# 16n-midijack.net
KiCad netlist of a schematic drawn in EAGLE
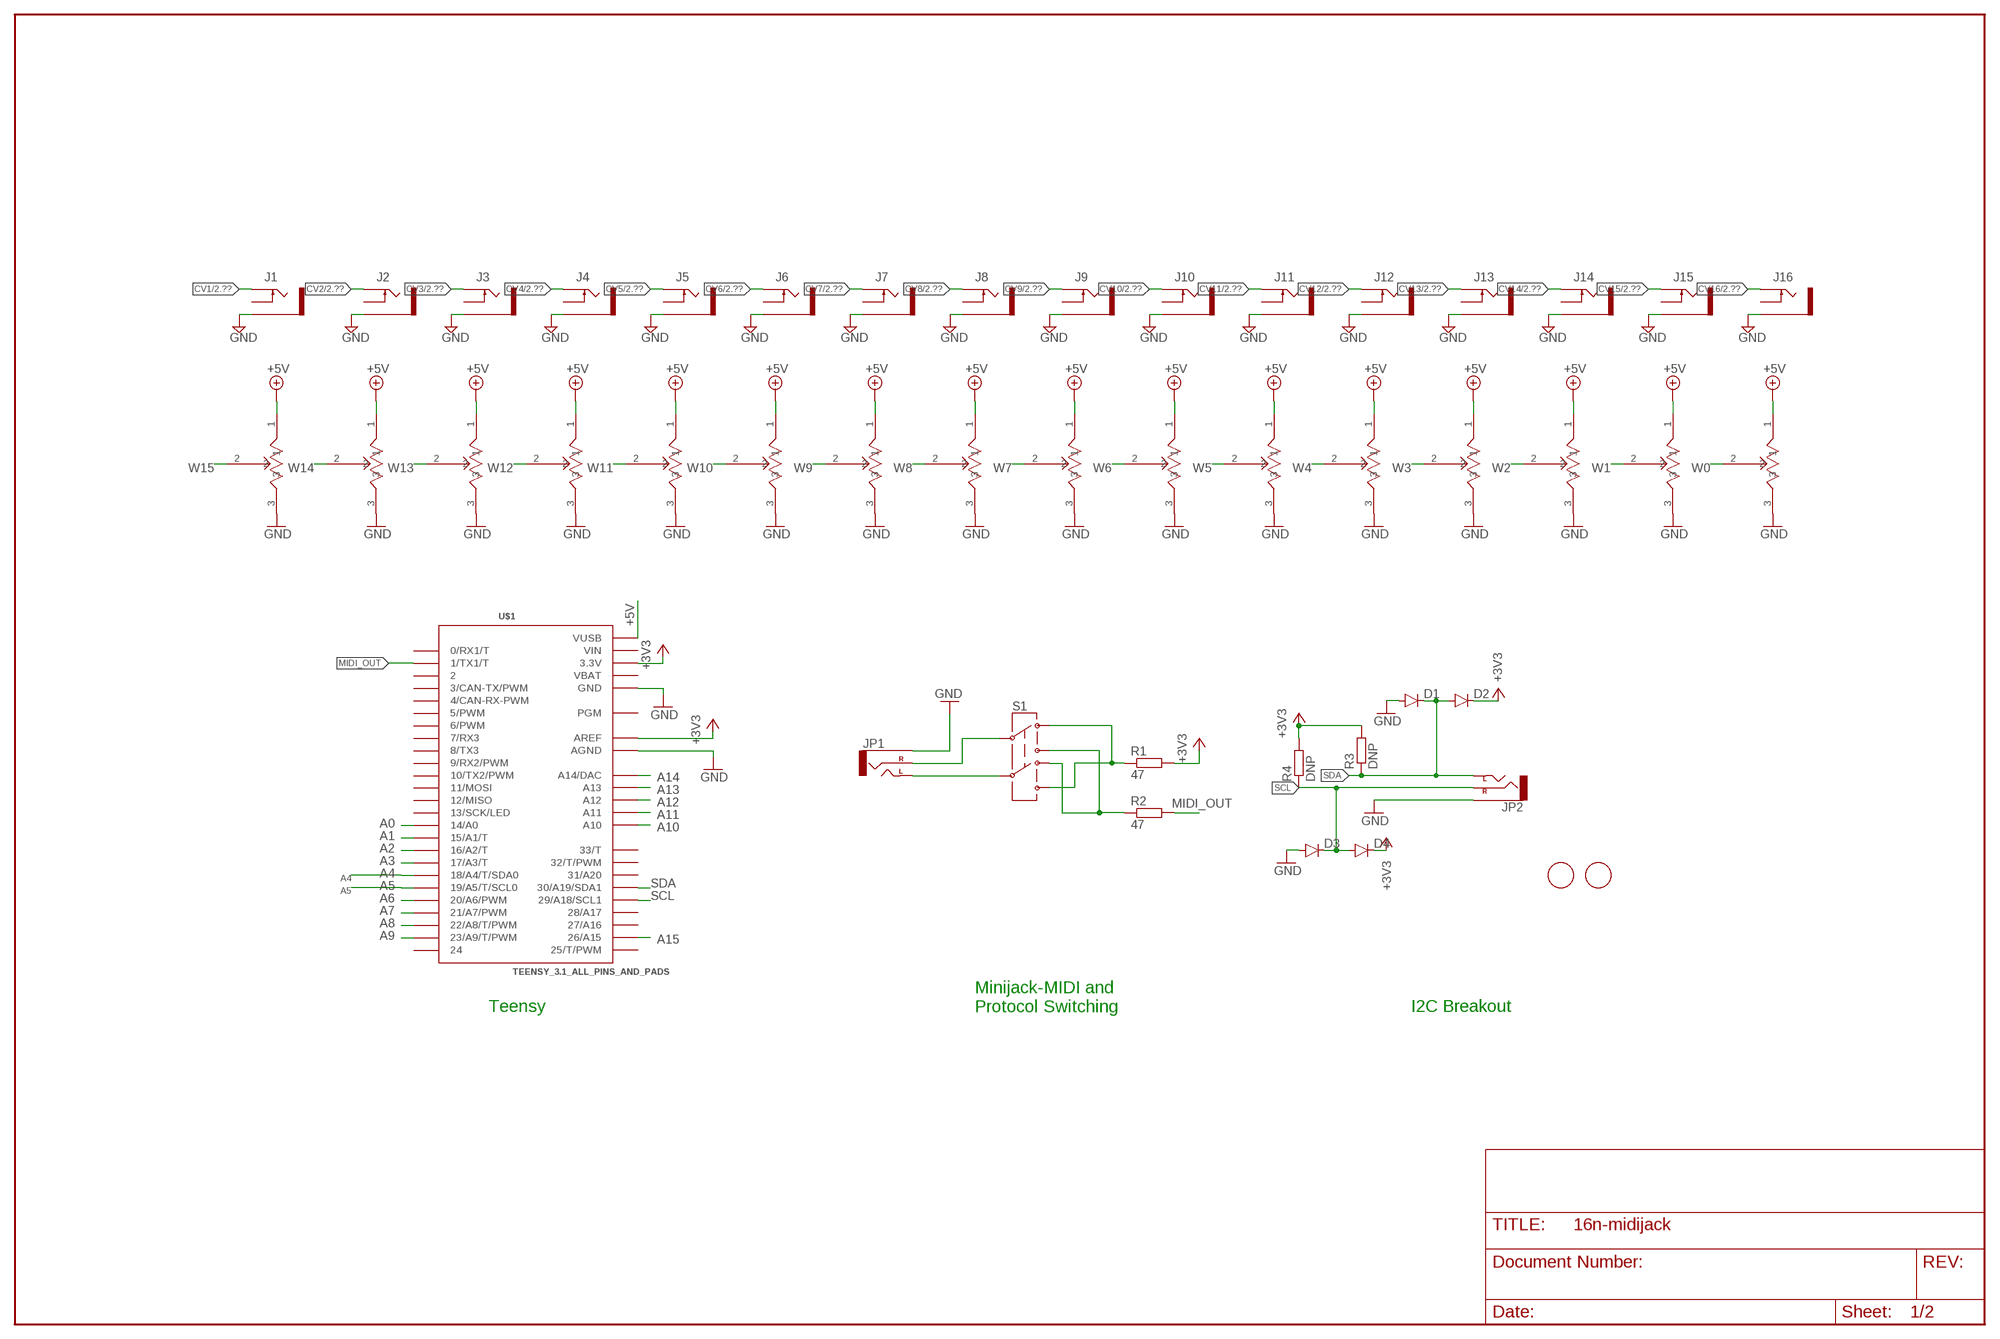
[diagram p0: schematic, sheet 1]
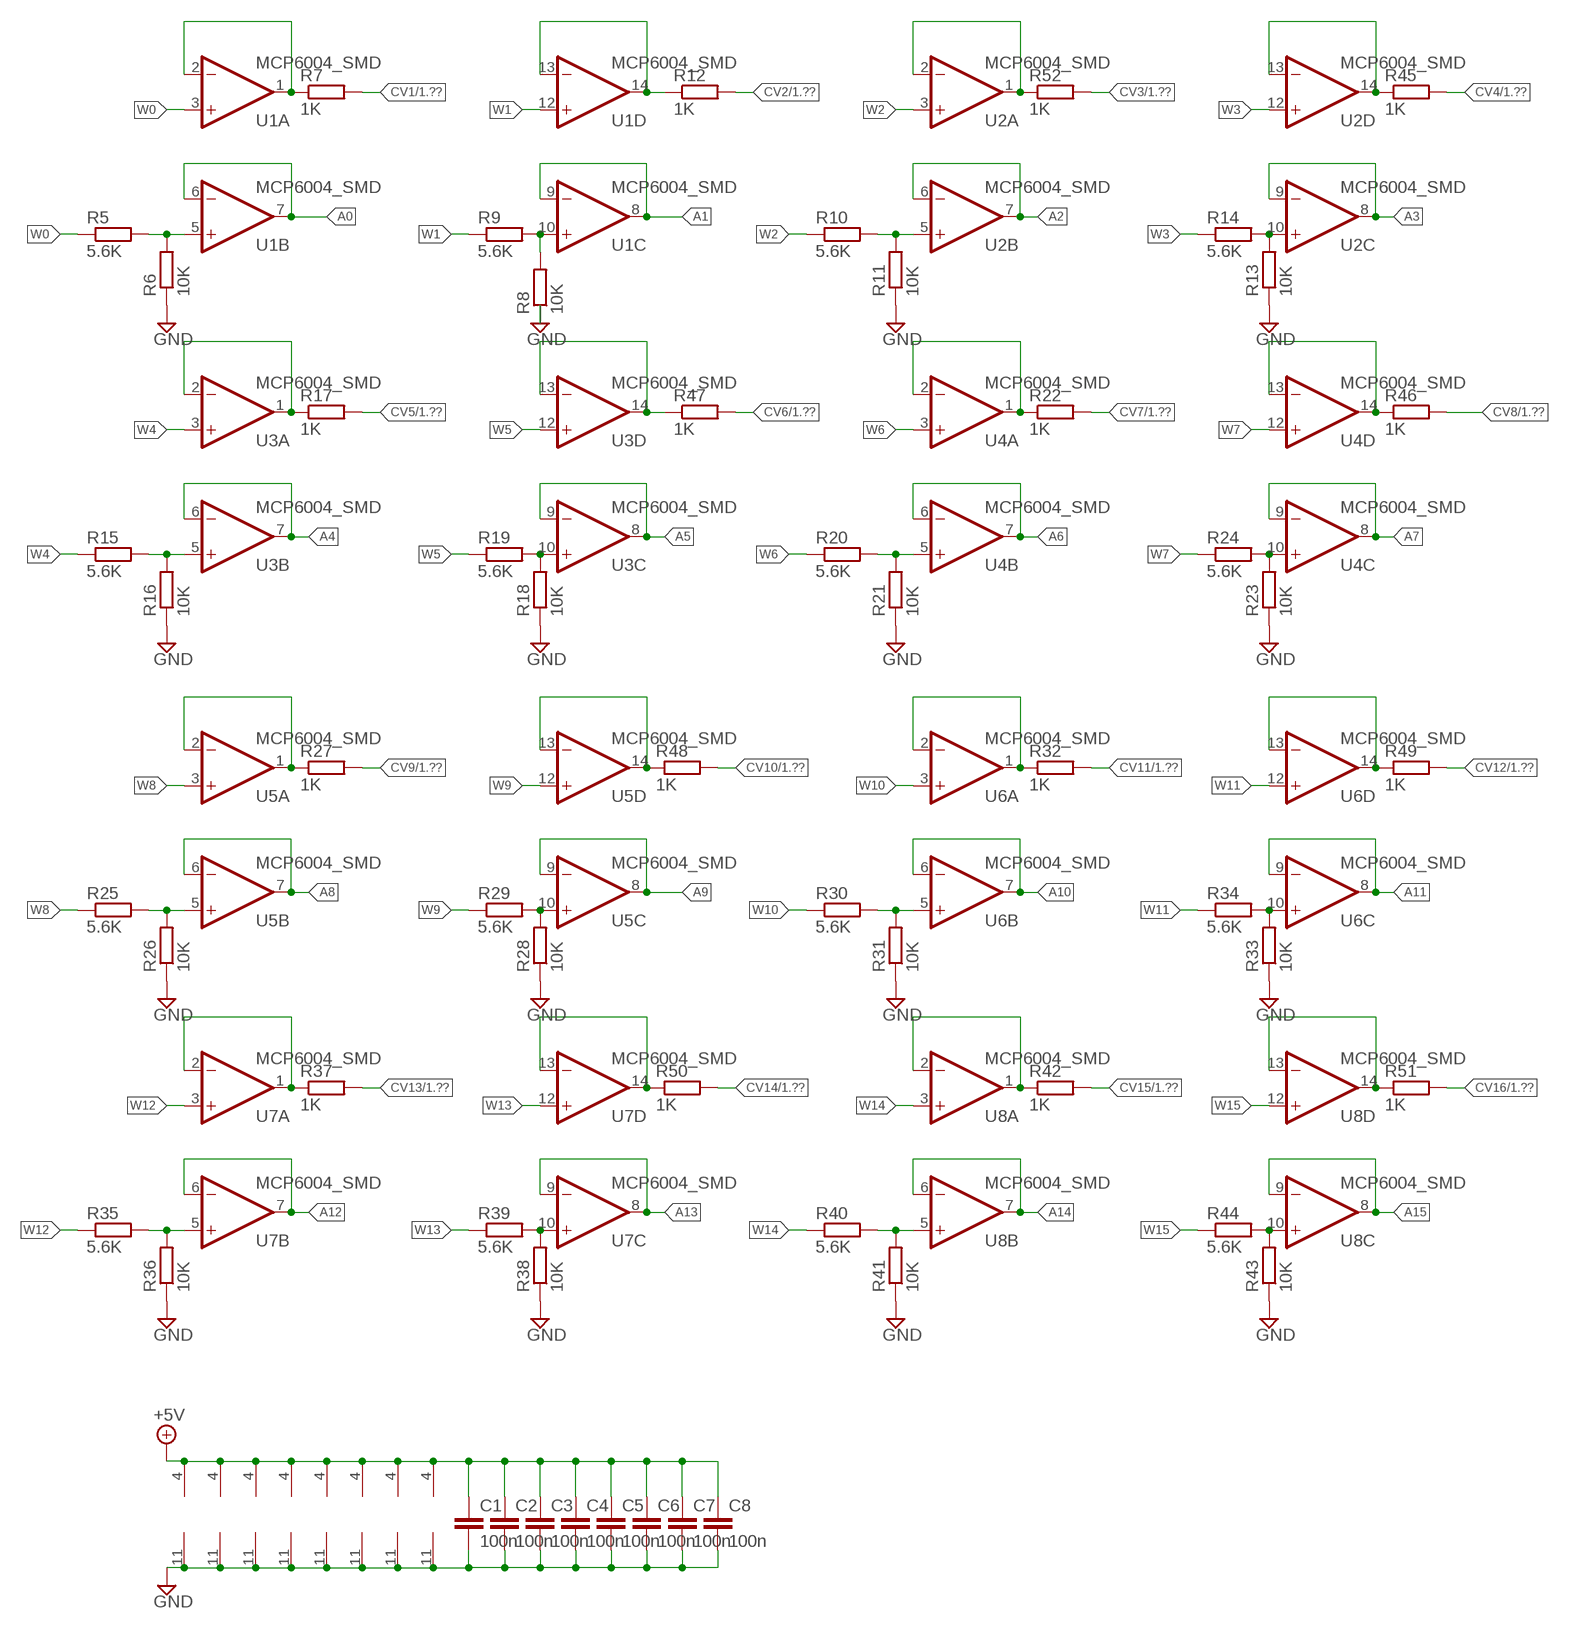
[diagram p1: schematic, sheet 2]

(export (version "E")
  (design (tool "Eeschema 10.0.6"))
  (components
    (comp (ref "C1")
      (value "100n")
      (footprint "eagle-import:C0805")
      (libsource (lib "eagle-import") (part "C-EUC0805"))
    )
    (comp (ref "C2")
      (value "100n")
      (footprint "eagle-import:C0805")
      (libsource (lib "eagle-import") (part "C-EUC0805"))
    )
    (comp (ref "C3")
      (value "100n")
      (footprint "eagle-import:C0805")
      (libsource (lib "eagle-import") (part "C-EUC0805"))
    )
    (comp (ref "C4")
      (value "100n")
      (footprint "eagle-import:C0805")
      (libsource (lib "eagle-import") (part "C-EUC0805"))
    )
    (comp (ref "C5")
      (value "100n")
      (footprint "eagle-import:C0805")
      (libsource (lib "eagle-import") (part "C-EUC0805"))
    )
    (comp (ref "C6")
      (value "100n")
      (footprint "eagle-import:C0805")
      (libsource (lib "eagle-import") (part "C-EUC0805"))
    )
    (comp (ref "C7")
      (value "100n")
      (footprint "eagle-import:C0805")
      (libsource (lib "eagle-import") (part "C-EUC0805"))
    )
    (comp (ref "C8")
      (value "100n")
      (footprint "eagle-import:C0805")
      (libsource (lib "eagle-import") (part "C-EUC0805"))
    )
    (comp (ref "R5")
      (value "5.6K")
      (footprint "eagle-import:R0805")
      (libsource (lib "eagle-import") (part "R-EU_R0805"))
    )
    (comp (ref "R6")
      (value "10K")
      (footprint "eagle-import:R0805")
      (libsource (lib "eagle-import") (part "R-EU_R0805"))
    )
    (comp (ref "R7")
      (value "1K")
      (footprint "eagle-import:R0805")
      (libsource (lib "eagle-import") (part "R-EU_R0805"))
    )
    (comp (ref "R8")
      (value "10K")
      (footprint "eagle-import:R0805")
      (libsource (lib "eagle-import") (part "R-EU_R0805"))
    )
    (comp (ref "R9")
      (value "5.6K")
      (footprint "eagle-import:R0805")
      (libsource (lib "eagle-import") (part "R-EU_R0805"))
    )
    (comp (ref "R10")
      (value "5.6K")
      (footprint "eagle-import:R0805")
      (libsource (lib "eagle-import") (part "R-EU_R0805"))
    )
    (comp (ref "R11")
      (value "10K")
      (footprint "eagle-import:R0805")
      (libsource (lib "eagle-import") (part "R-EU_R0805"))
    )
    (comp (ref "R12")
      (value "1K")
      (footprint "eagle-import:R0805")
      (libsource (lib "eagle-import") (part "R-EU_R0805"))
    )
    (comp (ref "R13")
      (value "10K")
      (footprint "eagle-import:R0805")
      (libsource (lib "eagle-import") (part "R-EU_R0805"))
    )
    (comp (ref "R14")
      (value "5.6K")
      (footprint "eagle-import:R0805")
      (libsource (lib "eagle-import") (part "R-EU_R0805"))
    )
    (comp (ref "R15")
      (value "5.6K")
      (footprint "eagle-import:R0805")
      (libsource (lib "eagle-import") (part "R-EU_R0805"))
    )
    (comp (ref "R16")
      (value "10K")
      (footprint "eagle-import:R0805")
      (libsource (lib "eagle-import") (part "R-EU_R0805"))
    )
    (comp (ref "R17")
      (value "1K")
      (footprint "eagle-import:R0805")
      (libsource (lib "eagle-import") (part "R-EU_R0805"))
    )
    (comp (ref "R18")
      (value "10K")
      (footprint "eagle-import:R0805")
      (libsource (lib "eagle-import") (part "R-EU_R0805"))
    )
    (comp (ref "R19")
      (value "5.6K")
      (footprint "eagle-import:R0805")
      (libsource (lib "eagle-import") (part "R-EU_R0805"))
    )
    (comp (ref "R20")
      (value "5.6K")
      (footprint "eagle-import:R0805")
      (libsource (lib "eagle-import") (part "R-EU_R0805"))
    )
    (comp (ref "R21")
      (value "10K")
      (footprint "eagle-import:R0805")
      (libsource (lib "eagle-import") (part "R-EU_R0805"))
    )
    (comp (ref "R22")
      (value "1K")
      (footprint "eagle-import:R0805")
      (libsource (lib "eagle-import") (part "R-EU_R0805"))
    )
    (comp (ref "R23")
      (value "10K")
      (footprint "eagle-import:R0805")
      (libsource (lib "eagle-import") (part "R-EU_R0805"))
    )
    (comp (ref "R24")
      (value "5.6K")
      (footprint "eagle-import:R0805")
      (libsource (lib "eagle-import") (part "R-EU_R0805"))
    )
    (comp (ref "R25")
      (value "5.6K")
      (footprint "eagle-import:R0805")
      (libsource (lib "eagle-import") (part "R-EU_R0805"))
    )
    (comp (ref "R26")
      (value "10K")
      (footprint "eagle-import:R0805")
      (libsource (lib "eagle-import") (part "R-EU_R0805"))
    )
    (comp (ref "R27")
      (value "1K")
      (footprint "eagle-import:R0805")
      (libsource (lib "eagle-import") (part "R-EU_R0805"))
    )
    (comp (ref "R28")
      (value "10K")
      (footprint "eagle-import:R0805")
      (libsource (lib "eagle-import") (part "R-EU_R0805"))
    )
    (comp (ref "R29")
      (value "5.6K")
      (footprint "eagle-import:R0805")
      (libsource (lib "eagle-import") (part "R-EU_R0805"))
    )
    (comp (ref "R30")
      (value "5.6K")
      (footprint "eagle-import:R0805")
      (libsource (lib "eagle-import") (part "R-EU_R0805"))
    )
    (comp (ref "R31")
      (value "10K")
      (footprint "eagle-import:R0805")
      (libsource (lib "eagle-import") (part "R-EU_R0805"))
    )
    (comp (ref "R32")
      (value "1K")
      (footprint "eagle-import:R0805")
      (libsource (lib "eagle-import") (part "R-EU_R0805"))
    )
    (comp (ref "R33")
      (value "10K")
      (footprint "eagle-import:R0805")
      (libsource (lib "eagle-import") (part "R-EU_R0805"))
    )
    (comp (ref "R34")
      (value "5.6K")
      (footprint "eagle-import:R0805")
      (libsource (lib "eagle-import") (part "R-EU_R0805"))
    )
    (comp (ref "R35")
      (value "5.6K")
      (footprint "eagle-import:R0805")
      (libsource (lib "eagle-import") (part "R-EU_R0805"))
    )
    (comp (ref "R36")
      (value "10K")
      (footprint "eagle-import:R0805")
      (libsource (lib "eagle-import") (part "R-EU_R0805"))
    )
    (comp (ref "R37")
      (value "1K")
      (footprint "eagle-import:R0805")
      (libsource (lib "eagle-import") (part "R-EU_R0805"))
    )
    (comp (ref "R38")
      (value "10K")
      (footprint "eagle-import:R0805")
      (libsource (lib "eagle-import") (part "R-EU_R0805"))
    )
    (comp (ref "R39")
      (value "5.6K")
      (footprint "eagle-import:R0805")
      (libsource (lib "eagle-import") (part "R-EU_R0805"))
    )
    (comp (ref "R40")
      (value "5.6K")
      (footprint "eagle-import:R0805")
      (libsource (lib "eagle-import") (part "R-EU_R0805"))
    )
    (comp (ref "R41")
      (value "10K")
      (footprint "eagle-import:R0805")
      (libsource (lib "eagle-import") (part "R-EU_R0805"))
    )
    (comp (ref "R42")
      (value "1K")
      (footprint "eagle-import:R0805")
      (libsource (lib "eagle-import") (part "R-EU_R0805"))
    )
    (comp (ref "R43")
      (value "10K")
      (footprint "eagle-import:R0805")
      (libsource (lib "eagle-import") (part "R-EU_R0805"))
    )
    (comp (ref "R44")
      (value "5.6K")
      (footprint "eagle-import:R0805")
      (libsource (lib "eagle-import") (part "R-EU_R0805"))
    )
    (comp (ref "R45")
      (value "1K")
      (footprint "eagle-import:R0805")
      (libsource (lib "eagle-import") (part "R-EU_R0805"))
    )
    (comp (ref "R46")
      (value "1K")
      (footprint "eagle-import:R0805")
      (libsource (lib "eagle-import") (part "R-EU_R0805"))
    )
    (comp (ref "R47")
      (value "1K")
      (footprint "eagle-import:R0805")
      (libsource (lib "eagle-import") (part "R-EU_R0805"))
    )
    (comp (ref "R48")
      (value "1K")
      (footprint "eagle-import:R0805")
      (libsource (lib "eagle-import") (part "R-EU_R0805"))
    )
    (comp (ref "R49")
      (value "1K")
      (footprint "eagle-import:R0805")
      (libsource (lib "eagle-import") (part "R-EU_R0805"))
    )
    (comp (ref "R50")
      (value "1K")
      (footprint "eagle-import:R0805")
      (libsource (lib "eagle-import") (part "R-EU_R0805"))
    )
    (comp (ref "R51")
      (value "1K")
      (footprint "eagle-import:R0805")
      (libsource (lib "eagle-import") (part "R-EU_R0805"))
    )
    (comp (ref "R52")
      (value "1K")
      (footprint "eagle-import:R0805")
      (libsource (lib "eagle-import") (part "R-EU_R0805"))
    )
    (comp (ref "U1")
      (value "MCP6004_SMD")
      (footprint "eagle-import:SO14")
      (libsource (lib "eagle-import") (part "MCP6004_SMD"))
    )
    (comp (ref "U2")
      (value "MCP6004_SMD")
      (footprint "eagle-import:SO14")
      (libsource (lib "eagle-import") (part "MCP6004_SMD"))
    )
    (comp (ref "U3")
      (value "MCP6004_SMD")
      (footprint "eagle-import:SO14")
      (libsource (lib "eagle-import") (part "MCP6004_SMD"))
    )
    (comp (ref "U4")
      (value "MCP6004_SMD")
      (footprint "eagle-import:SO14")
      (libsource (lib "eagle-import") (part "MCP6004_SMD"))
    )
    (comp (ref "U5")
      (value "MCP6004_SMD")
      (footprint "eagle-import:SO14")
      (libsource (lib "eagle-import") (part "MCP6004_SMD"))
    )
    (comp (ref "U6")
      (value "MCP6004_SMD")
      (footprint "eagle-import:SO14")
      (libsource (lib "eagle-import") (part "MCP6004_SMD"))
    )
    (comp (ref "U7")
      (value "MCP6004_SMD")
      (footprint "eagle-import:SO14")
      (libsource (lib "eagle-import") (part "MCP6004_SMD"))
    )
    (comp (ref "U8")
      (value "MCP6004_SMD")
      (footprint "eagle-import:SO14")
      (libsource (lib "eagle-import") (part "MCP6004_SMD"))
    )
    (comp (ref "D1")
      (value "DIODESOD123")
      (footprint "eagle-import:SOD-123")
      (libsource (lib "eagle-import") (part "DIODESOD123"))
    )
    (comp (ref "D2")
      (value "DIODESOD123")
      (footprint "eagle-import:SOD-123")
      (libsource (lib "eagle-import") (part "DIODESOD123"))
    )
    (comp (ref "D3")
      (value "DIODESOD123")
      (footprint "eagle-import:SOD-123")
      (libsource (lib "eagle-import") (part "DIODESOD123"))
    )
    (comp (ref "D4")
      (value "DIODESOD123")
      (footprint "eagle-import:SOD-123")
      (libsource (lib "eagle-import") (part "DIODESOD123"))
    )
    (comp (ref "FID1")
      (value "FIDUCIAL")
      (footprint "eagle-import:FIDUCIAL_1MM")
      (libsource (lib "eagle-import") (part "FIDUCIAL"))
    )
    (comp (ref "FID2")
      (value "FIDUCIAL")
      (footprint "eagle-import:FIDUCIAL_1MM")
      (libsource (lib "eagle-import") (part "FIDUCIAL"))
    )
    (comp (ref "J1")
      (value "PJ302M")
      (footprint "eagle-import:PJ302M")
      (libsource (lib "eagle-import") (part "PJ302M"))
    )
    (comp (ref "J2")
      (value "PJ302M")
      (footprint "eagle-import:PJ302M")
      (libsource (lib "eagle-import") (part "PJ302M"))
    )
    (comp (ref "J3")
      (value "PJ302M")
      (footprint "eagle-import:PJ302M")
      (libsource (lib "eagle-import") (part "PJ302M"))
    )
    (comp (ref "J4")
      (value "PJ302M")
      (footprint "eagle-import:PJ302M")
      (libsource (lib "eagle-import") (part "PJ302M"))
    )
    (comp (ref "J5")
      (value "PJ302M")
      (footprint "eagle-import:PJ302M")
      (libsource (lib "eagle-import") (part "PJ302M"))
    )
    (comp (ref "J6")
      (value "PJ302M")
      (footprint "eagle-import:PJ302M")
      (libsource (lib "eagle-import") (part "PJ302M"))
    )
    (comp (ref "J7")
      (value "PJ302M")
      (footprint "eagle-import:PJ302M")
      (libsource (lib "eagle-import") (part "PJ302M"))
    )
    (comp (ref "J8")
      (value "PJ302M")
      (footprint "eagle-import:PJ302M")
      (libsource (lib "eagle-import") (part "PJ302M"))
    )
    (comp (ref "J9")
      (value "PJ302M")
      (footprint "eagle-import:PJ302M")
      (libsource (lib "eagle-import") (part "PJ302M"))
    )
    (comp (ref "J10")
      (value "PJ302M")
      (footprint "eagle-import:PJ302M")
      (libsource (lib "eagle-import") (part "PJ302M"))
    )
    (comp (ref "J11")
      (value "PJ302M")
      (footprint "eagle-import:PJ302M")
      (libsource (lib "eagle-import") (part "PJ302M"))
    )
    (comp (ref "J12")
      (value "PJ302M")
      (footprint "eagle-import:PJ302M")
      (libsource (lib "eagle-import") (part "PJ302M"))
    )
    (comp (ref "J13")
      (value "PJ302M")
      (footprint "eagle-import:PJ302M")
      (libsource (lib "eagle-import") (part "PJ302M"))
    )
    (comp (ref "J14")
      (value "PJ302M")
      (footprint "eagle-import:PJ302M")
      (libsource (lib "eagle-import") (part "PJ302M"))
    )
    (comp (ref "J15")
      (value "PJ302M")
      (footprint "eagle-import:PJ302M")
      (libsource (lib "eagle-import") (part "PJ302M"))
    )
    (comp (ref "J16")
      (value "PJ302M")
      (footprint "eagle-import:PJ302M")
      (libsource (lib "eagle-import") (part "PJ302M"))
    )
    (comp (ref "JP1")
      (value "AUDIO-JACKPTH")
      (footprint "eagle-import:AUDIO-JACK")
      (libsource (lib "eagle-import") (part "AUDIO-JACKPTH"))
    )
    (comp (ref "JP2")
      (value "AUDIO-JACKPTH")
      (footprint "eagle-import:AUDIO-JACK")
      (libsource (lib "eagle-import") (part "AUDIO-JACKPTH"))
    )
    (comp (ref "R1")
      (value "47")
      (footprint "eagle-import:R0805")
      (libsource (lib "eagle-import") (part "R-EU_R0805"))
    )
    (comp (ref "R2")
      (value "47")
      (footprint "eagle-import:R0805")
      (libsource (lib "eagle-import") (part "R-EU_R0805"))
    )
    (comp (ref "R3")
      (value "DNP")
      (footprint "eagle-import:R0805")
      (libsource (lib "eagle-import") (part "R-EU_R0805"))
    )
    (comp (ref "R4")
      (value "DNP")
      (footprint "eagle-import:R0805")
      (libsource (lib "eagle-import") (part "R-EU_R0805"))
    )
    (comp (ref "S1")
      (value "SWITCH-DPDTEG2211")
      (footprint "eagle-import:EG2211")
      (libsource (lib "eagle-import") (part "SWITCH-DPDTEG2211"))
    )
    (comp (ref "U$1")
      (value "TEENSY_3.1_ALL_PINS_AND_PADS")
      (footprint "eagle-import:TEENSY_3.1_ALLPINS")
      (libsource (lib "eagle-import") (part "TEENSY_3.1_ALL_PINS_AND_PADS"))
    )
    (comp (ref "U$2")
      (value "SLIDEPOT-ALPS-60MM")
      (footprint "eagle-import:RS6011SP600")
      (libsource (lib "eagle-import") (part "SLIDEPOT-ALPS-60MM"))
    )
    (comp (ref "U$3")
      (value "SLIDEPOT-ALPS-60MM")
      (footprint "eagle-import:RS6011SP600")
      (libsource (lib "eagle-import") (part "SLIDEPOT-ALPS-60MM"))
    )
    (comp (ref "U$4")
      (value "SLIDEPOT-ALPS-60MM")
      (footprint "eagle-import:RS6011SP600")
      (libsource (lib "eagle-import") (part "SLIDEPOT-ALPS-60MM"))
    )
    (comp (ref "U$5")
      (value "SLIDEPOT-ALPS-60MM")
      (footprint "eagle-import:RS6011SP600")
      (libsource (lib "eagle-import") (part "SLIDEPOT-ALPS-60MM"))
    )
    (comp (ref "U$6")
      (value "SLIDEPOT-ALPS-60MM")
      (footprint "eagle-import:RS6011SP600")
      (libsource (lib "eagle-import") (part "SLIDEPOT-ALPS-60MM"))
    )
    (comp (ref "U$7")
      (value "SLIDEPOT-ALPS-60MM")
      (footprint "eagle-import:RS6011SP600")
      (libsource (lib "eagle-import") (part "SLIDEPOT-ALPS-60MM"))
    )
    (comp (ref "U$8")
      (value "SLIDEPOT-ALPS-60MM")
      (footprint "eagle-import:RS6011SP600")
      (libsource (lib "eagle-import") (part "SLIDEPOT-ALPS-60MM"))
    )
    (comp (ref "U$9")
      (value "SLIDEPOT-ALPS-60MM")
      (footprint "eagle-import:RS6011SP600")
      (libsource (lib "eagle-import") (part "SLIDEPOT-ALPS-60MM"))
    )
    (comp (ref "U$10")
      (value "SLIDEPOT-ALPS-60MM")
      (footprint "eagle-import:RS6011SP600")
      (libsource (lib "eagle-import") (part "SLIDEPOT-ALPS-60MM"))
    )
    (comp (ref "U$11")
      (value "SLIDEPOT-ALPS-60MM")
      (footprint "eagle-import:RS6011SP600")
      (libsource (lib "eagle-import") (part "SLIDEPOT-ALPS-60MM"))
    )
    (comp (ref "U$12")
      (value "SLIDEPOT-ALPS-60MM")
      (footprint "eagle-import:RS6011SP600")
      (libsource (lib "eagle-import") (part "SLIDEPOT-ALPS-60MM"))
    )
    (comp (ref "U$13")
      (value "SLIDEPOT-ALPS-60MM")
      (footprint "eagle-import:RS6011SP600")
      (libsource (lib "eagle-import") (part "SLIDEPOT-ALPS-60MM"))
    )
    (comp (ref "U$14")
      (value "SLIDEPOT-ALPS-60MM")
      (footprint "eagle-import:RS6011SP600")
      (libsource (lib "eagle-import") (part "SLIDEPOT-ALPS-60MM"))
    )
    (comp (ref "U$15")
      (value "SLIDEPOT-ALPS-60MM")
      (footprint "eagle-import:RS6011SP600")
      (libsource (lib "eagle-import") (part "SLIDEPOT-ALPS-60MM"))
    )
    (comp (ref "U$16")
      (value "SLIDEPOT-ALPS-60MM")
      (footprint "eagle-import:RS6011SP600")
      (libsource (lib "eagle-import") (part "SLIDEPOT-ALPS-60MM"))
    )
    (comp (ref "U$17")
      (value "SLIDEPOT-ALPS-60MM")
      (footprint "eagle-import:RS6011SP600")
      (libsource (lib "eagle-import") (part "SLIDEPOT-ALPS-60MM"))
    )
  )
  (nets
    (net (code "1") (name "+3V3") (class "Default")
      (node (ref "D2") (pin "C") (pinfunction "C_C") (pintype "passive"))
      (node (ref "D4") (pin "C") (pinfunction "C_C") (pintype "passive"))
      (node (ref "R1") (pin "2") (pinfunction "2_2") (pintype "passive"))
      (node (ref "R3") (pin "2") (pinfunction "2_2") (pintype "passive"))
      (node (ref "R4") (pin "2") (pinfunction "2_2") (pintype "passive"))
      (node (ref "U$1") (pin "3.3V") (pinfunction "3.3V_3.3V") (pintype "power_in"))
      (node (ref "U$1") (pin "3.3V1") (pinfunction "3.3V_3.3V1") (pintype "power_in"))
      (node (ref "U$1") (pin "3.3V2") (pinfunction "3.3V_3.3V2") (pintype "power_in"))
      (node (ref "U$1") (pin "AREF") (pinfunction "AREF_AREF") (pintype "power_in"))
    )
    (net (code "2") (name "+5V") (class "Default")
      (node (ref "C1") (pin "1") (pinfunction "1_1") (pintype "passive"))
      (node (ref "C2") (pin "1") (pinfunction "1_1") (pintype "passive"))
      (node (ref "C3") (pin "1") (pinfunction "1_1") (pintype "passive"))
      (node (ref "C4") (pin "1") (pinfunction "1_1") (pintype "passive"))
      (node (ref "C5") (pin "1") (pinfunction "1_1") (pintype "passive"))
      (node (ref "C6") (pin "1") (pinfunction "1_1") (pintype "passive"))
      (node (ref "C7") (pin "1") (pinfunction "1_1") (pintype "passive"))
      (node (ref "C8") (pin "1") (pinfunction "1_1") (pintype "passive"))
      (node (ref "U$1") (pin "VUSB") (pinfunction "VUSB_VUSB") (pintype "power_in"))
      (node (ref "U$10") (pin "1") (pinfunction "1_1") (pintype "bidirectional"))
      (node (ref "U$11") (pin "1") (pinfunction "1_1") (pintype "bidirectional"))
      (node (ref "U$12") (pin "1") (pinfunction "1_1") (pintype "bidirectional"))
      (node (ref "U$13") (pin "1") (pinfunction "1_1") (pintype "bidirectional"))
      (node (ref "U$14") (pin "1") (pinfunction "1_1") (pintype "bidirectional"))
      (node (ref "U$15") (pin "1") (pinfunction "1_1") (pintype "bidirectional"))
      (node (ref "U$16") (pin "1") (pinfunction "1_1") (pintype "bidirectional"))
      (node (ref "U$17") (pin "1") (pinfunction "1_1") (pintype "bidirectional"))
      (node (ref "U$2") (pin "1") (pinfunction "1_1") (pintype "bidirectional"))
      (node (ref "U$3") (pin "1") (pinfunction "1_1") (pintype "bidirectional"))
      (node (ref "U$4") (pin "1") (pinfunction "1_1") (pintype "bidirectional"))
      (node (ref "U$5") (pin "1") (pinfunction "1_1") (pintype "bidirectional"))
      (node (ref "U$6") (pin "1") (pinfunction "1_1") (pintype "bidirectional"))
      (node (ref "U$7") (pin "1") (pinfunction "1_1") (pintype "bidirectional"))
      (node (ref "U$8") (pin "1") (pinfunction "1_1") (pintype "bidirectional"))
      (node (ref "U$9") (pin "1") (pinfunction "1_1") (pintype "bidirectional"))
      (node (ref "U1") (pin "4") (pinfunction "V+_4") (pintype "power_in"))
      (node (ref "U2") (pin "4") (pinfunction "V+_4") (pintype "power_in"))
      (node (ref "U3") (pin "4") (pinfunction "V+_4") (pintype "power_in"))
      (node (ref "U4") (pin "4") (pinfunction "V+_4") (pintype "power_in"))
      (node (ref "U5") (pin "4") (pinfunction "V+_4") (pintype "power_in"))
      (node (ref "U6") (pin "4") (pinfunction "V+_4") (pintype "power_in"))
      (node (ref "U7") (pin "4") (pinfunction "V+_4") (pintype "power_in"))
      (node (ref "U8") (pin "4") (pinfunction "V+_4") (pintype "power_in"))
    )
    (net (code "3") (name "A0") (class "Default")
      (node (ref "U$1") (pin "14/A0") (pinfunction "14/A0_14/A0") (pintype "bidirectional"))
      (node (ref "U1") (pin "6") (pinfunction "-IN_6") (pintype "input"))
      (node (ref "U1") (pin "7") (pinfunction "OUT_7") (pintype "output"))
    )
    (net (code "4") (name "A1") (class "Default")
      (node (ref "U$1") (pin "15/A1") (pinfunction "15/A1/T_15/A1") (pintype "bidirectional"))
      (node (ref "U1") (pin "8") (pinfunction "OUT_8") (pintype "output"))
      (node (ref "U1") (pin "9") (pinfunction "-IN_9") (pintype "input"))
    )
    (net (code "5") (name "A2") (class "Default")
      (node (ref "U$1") (pin "16/A2") (pinfunction "16/A2/T_16/A2") (pintype "bidirectional"))
      (node (ref "U2") (pin "6") (pinfunction "-IN_6") (pintype "input"))
      (node (ref "U2") (pin "7") (pinfunction "OUT_7") (pintype "output"))
    )
    (net (code "6") (name "A3") (class "Default")
      (node (ref "U$1") (pin "17/A3") (pinfunction "17/A3/T_17/A3") (pintype "bidirectional"))
      (node (ref "U2") (pin "8") (pinfunction "OUT_8") (pintype "output"))
      (node (ref "U2") (pin "9") (pinfunction "-IN_9") (pintype "input"))
    )
    (net (code "7") (name "A4") (class "Default")
      (node (ref "U$1") (pin "18/A4") (pinfunction "18/A4/T/SDA0_18/A4") (pintype "bidirectional"))
      (node (ref "U3") (pin "6") (pinfunction "-IN_6") (pintype "input"))
      (node (ref "U3") (pin "7") (pinfunction "OUT_7") (pintype "output"))
    )
    (net (code "8") (name "A5") (class "Default")
      (node (ref "U$1") (pin "19/A5") (pinfunction "19/A5/T/SCL0_19/A5") (pintype "bidirectional"))
      (node (ref "U3") (pin "8") (pinfunction "OUT_8") (pintype "output"))
      (node (ref "U3") (pin "9") (pinfunction "-IN_9") (pintype "input"))
    )
    (net (code "9") (name "A6") (class "Default")
      (node (ref "U$1") (pin "20/A6") (pinfunction "20/A6/PWM_20/A6") (pintype "bidirectional"))
      (node (ref "U4") (pin "6") (pinfunction "-IN_6") (pintype "input"))
      (node (ref "U4") (pin "7") (pinfunction "OUT_7") (pintype "output"))
    )
    (net (code "10") (name "A7") (class "Default")
      (node (ref "U$1") (pin "21/A7") (pinfunction "21/A7/PWM_21/A7") (pintype "bidirectional"))
      (node (ref "U4") (pin "8") (pinfunction "OUT_8") (pintype "output"))
      (node (ref "U4") (pin "9") (pinfunction "-IN_9") (pintype "input"))
    )
    (net (code "11") (name "A8") (class "Default")
      (node (ref "U$1") (pin "22/A8") (pinfunction "22/A8/T/PWM_22/A8") (pintype "bidirectional"))
      (node (ref "U5") (pin "6") (pinfunction "-IN_6") (pintype "input"))
      (node (ref "U5") (pin "7") (pinfunction "OUT_7") (pintype "output"))
    )
    (net (code "12") (name "A9") (class "Default")
      (node (ref "U$1") (pin "23/A9") (pinfunction "23/A9/T/PWM_23/A9") (pintype "bidirectional"))
      (node (ref "U5") (pin "8") (pinfunction "OUT_8") (pintype "output"))
      (node (ref "U5") (pin "9") (pinfunction "-IN_9") (pintype "input"))
    )
    (net (code "13") (name "A10") (class "Default")
      (node (ref "U$1") (pin "A10") (pinfunction "A10_A10") (pintype "bidirectional"))
      (node (ref "U6") (pin "6") (pinfunction "-IN_6") (pintype "input"))
      (node (ref "U6") (pin "7") (pinfunction "OUT_7") (pintype "output"))
    )
    (net (code "14") (name "A11") (class "Default")
      (node (ref "U$1") (pin "A11") (pinfunction "A11_A11") (pintype "bidirectional"))
      (node (ref "U6") (pin "8") (pinfunction "OUT_8") (pintype "output"))
      (node (ref "U6") (pin "9") (pinfunction "-IN_9") (pintype "input"))
    )
    (net (code "15") (name "A12") (class "Default")
      (node (ref "U$1") (pin "A12") (pinfunction "A12_A12") (pintype "bidirectional"))
      (node (ref "U7") (pin "6") (pinfunction "-IN_6") (pintype "input"))
      (node (ref "U7") (pin "7") (pinfunction "OUT_7") (pintype "output"))
    )
    (net (code "16") (name "A13") (class "Default")
      (node (ref "U$1") (pin "A13") (pinfunction "A13_A13") (pintype "bidirectional"))
      (node (ref "U7") (pin "8") (pinfunction "OUT_8") (pintype "output"))
      (node (ref "U7") (pin "9") (pinfunction "-IN_9") (pintype "input"))
    )
    (net (code "17") (name "A14") (class "Default")
      (node (ref "U$1") (pin "A14") (pinfunction "A14/DAC_A14") (pintype "bidirectional"))
      (node (ref "U8") (pin "6") (pinfunction "-IN_6") (pintype "input"))
      (node (ref "U8") (pin "7") (pinfunction "OUT_7") (pintype "output"))
    )
    (net (code "18") (name "A15") (class "Default")
      (node (ref "U$1") (pin "26") (pinfunction "26/A15_26") (pintype "bidirectional"))
      (node (ref "U8") (pin "8") (pinfunction "OUT_8") (pintype "output"))
      (node (ref "U8") (pin "9") (pinfunction "-IN_9") (pintype "input"))
    )
    (net (code "19") (name "CV1") (class "Default")
      (node (ref "J1") (pin "TIP") (pinfunction "TIP_TIP") (pintype "passive"))
      (node (ref "R7") (pin "2") (pinfunction "2_2") (pintype "passive"))
    )
    (net (code "20") (name "CV2") (class "Default")
      (node (ref "J2") (pin "TIP") (pinfunction "TIP_TIP") (pintype "passive"))
      (node (ref "R12") (pin "2") (pinfunction "2_2") (pintype "passive"))
    )
    (net (code "21") (name "CV3") (class "Default")
      (node (ref "J3") (pin "TIP") (pinfunction "TIP_TIP") (pintype "passive"))
      (node (ref "R52") (pin "2") (pinfunction "2_2") (pintype "passive"))
    )
    (net (code "22") (name "CV4") (class "Default")
      (node (ref "J4") (pin "TIP") (pinfunction "TIP_TIP") (pintype "passive"))
      (node (ref "R45") (pin "2") (pinfunction "2_2") (pintype "passive"))
    )
    (net (code "23") (name "CV5") (class "Default")
      (node (ref "J5") (pin "TIP") (pinfunction "TIP_TIP") (pintype "passive"))
      (node (ref "R17") (pin "2") (pinfunction "2_2") (pintype "passive"))
    )
    (net (code "24") (name "CV6") (class "Default")
      (node (ref "J6") (pin "TIP") (pinfunction "TIP_TIP") (pintype "passive"))
      (node (ref "R47") (pin "2") (pinfunction "2_2") (pintype "passive"))
    )
    (net (code "25") (name "CV7") (class "Default")
      (node (ref "J7") (pin "TIP") (pinfunction "TIP_TIP") (pintype "passive"))
      (node (ref "R22") (pin "2") (pinfunction "2_2") (pintype "passive"))
    )
    (net (code "26") (name "CV8") (class "Default")
      (node (ref "J8") (pin "TIP") (pinfunction "TIP_TIP") (pintype "passive"))
      (node (ref "R46") (pin "2") (pinfunction "2_2") (pintype "passive"))
    )
    (net (code "27") (name "CV9") (class "Default")
      (node (ref "J9") (pin "TIP") (pinfunction "TIP_TIP") (pintype "passive"))
      (node (ref "R27") (pin "2") (pinfunction "2_2") (pintype "passive"))
    )
    (net (code "28") (name "CV10") (class "Default")
      (node (ref "J10") (pin "TIP") (pinfunction "TIP_TIP") (pintype "passive"))
      (node (ref "R48") (pin "2") (pinfunction "2_2") (pintype "passive"))
    )
    (net (code "29") (name "CV11") (class "Default")
      (node (ref "J11") (pin "TIP") (pinfunction "TIP_TIP") (pintype "passive"))
      (node (ref "R32") (pin "2") (pinfunction "2_2") (pintype "passive"))
    )
    (net (code "30") (name "CV12") (class "Default")
      (node (ref "J12") (pin "TIP") (pinfunction "TIP_TIP") (pintype "passive"))
      (node (ref "R49") (pin "2") (pinfunction "2_2") (pintype "passive"))
    )
    (net (code "31") (name "CV13") (class "Default")
      (node (ref "J13") (pin "TIP") (pinfunction "TIP_TIP") (pintype "passive"))
      (node (ref "R37") (pin "2") (pinfunction "2_2") (pintype "passive"))
    )
    (net (code "32") (name "CV14") (class "Default")
      (node (ref "J14") (pin "TIP") (pinfunction "TIP_TIP") (pintype "passive"))
      (node (ref "R50") (pin "2") (pinfunction "2_2") (pintype "passive"))
    )
    (net (code "33") (name "CV15") (class "Default")
      (node (ref "J15") (pin "TIP") (pinfunction "TIP_TIP") (pintype "passive"))
      (node (ref "R42") (pin "2") (pinfunction "2_2") (pintype "passive"))
    )
    (net (code "34") (name "CV16") (class "Default")
      (node (ref "J16") (pin "TIP") (pinfunction "TIP_TIP") (pintype "passive"))
      (node (ref "R51") (pin "2") (pinfunction "2_2") (pintype "passive"))
    )
    (net (code "35") (name "GND") (class "Default")
      (node (ref "C1") (pin "2") (pinfunction "2_2") (pintype "passive"))
      (node (ref "C2") (pin "2") (pinfunction "2_2") (pintype "passive"))
      (node (ref "C3") (pin "2") (pinfunction "2_2") (pintype "passive"))
      (node (ref "C4") (pin "2") (pinfunction "2_2") (pintype "passive"))
      (node (ref "C5") (pin "2") (pinfunction "2_2") (pintype "passive"))
      (node (ref "C6") (pin "2") (pinfunction "2_2") (pintype "passive"))
      (node (ref "C7") (pin "2") (pinfunction "2_2") (pintype "passive"))
      (node (ref "C8") (pin "2") (pinfunction "2_2") (pintype "passive"))
      (node (ref "D1") (pin "A") (pinfunction "A_A") (pintype "passive"))
      (node (ref "D3") (pin "A") (pinfunction "A_A") (pintype "passive"))
      (node (ref "J1") (pin "GND") (pinfunction "SLEEVE_GND") (pintype "passive"))
      (node (ref "J10") (pin "GND") (pinfunction "SLEEVE_GND") (pintype "passive"))
      (node (ref "J11") (pin "GND") (pinfunction "SLEEVE_GND") (pintype "passive"))
      (node (ref "J12") (pin "GND") (pinfunction "SLEEVE_GND") (pintype "passive"))
      (node (ref "J13") (pin "GND") (pinfunction "SLEEVE_GND") (pintype "passive"))
      (node (ref "J14") (pin "GND") (pinfunction "SLEEVE_GND") (pintype "passive"))
      (node (ref "J15") (pin "GND") (pinfunction "SLEEVE_GND") (pintype "passive"))
      (node (ref "J16") (pin "GND") (pinfunction "SLEEVE_GND") (pintype "passive"))
      (node (ref "J2") (pin "GND") (pinfunction "SLEEVE_GND") (pintype "passive"))
      (node (ref "J3") (pin "GND") (pinfunction "SLEEVE_GND") (pintype "passive"))
      (node (ref "J4") (pin "GND") (pinfunction "SLEEVE_GND") (pintype "passive"))
      (node (ref "J5") (pin "GND") (pinfunction "SLEEVE_GND") (pintype "passive"))
      (node (ref "J6") (pin "GND") (pinfunction "SLEEVE_GND") (pintype "passive"))
      (node (ref "J7") (pin "GND") (pinfunction "SLEEVE_GND") (pintype "passive"))
      (node (ref "J8") (pin "GND") (pinfunction "SLEEVE_GND") (pintype "passive"))
      (node (ref "J9") (pin "GND") (pinfunction "SLEEVE_GND") (pintype "passive"))
      (node (ref "JP1") (pin "SLEEVE") (pinfunction "SLEEVE_SLEEVE") (pintype "bidirectional"))
      (node (ref "JP2") (pin "SLEEVE") (pinfunction "SLEEVE_SLEEVE") (pintype "bidirectional"))
      (node (ref "R11") (pin "1") (pinfunction "1_1") (pintype "passive"))
      (node (ref "R13") (pin "1") (pinfunction "1_1") (pintype "passive"))
      (node (ref "R16") (pin "1") (pinfunction "1_1") (pintype "passive"))
      (node (ref "R18") (pin "1") (pinfunction "1_1") (pintype "passive"))
      (node (ref "R21") (pin "1") (pinfunction "1_1") (pintype "passive"))
      (node (ref "R23") (pin "1") (pinfunction "1_1") (pintype "passive"))
      (node (ref "R26") (pin "1") (pinfunction "1_1") (pintype "passive"))
      (node (ref "R28") (pin "1") (pinfunction "1_1") (pintype "passive"))
      (node (ref "R31") (pin "1") (pinfunction "1_1") (pintype "passive"))
      (node (ref "R33") (pin "1") (pinfunction "1_1") (pintype "passive"))
      (node (ref "R36") (pin "1") (pinfunction "1_1") (pintype "passive"))
      (node (ref "R38") (pin "1") (pinfunction "1_1") (pintype "passive"))
      (node (ref "R41") (pin "1") (pinfunction "1_1") (pintype "passive"))
      (node (ref "R43") (pin "1") (pinfunction "1_1") (pintype "passive"))
      (node (ref "R6") (pin "1") (pinfunction "1_1") (pintype "passive"))
      (node (ref "R8") (pin "1") (pinfunction "1_1") (pintype "passive"))
      (node (ref "U$1") (pin "AGND") (pinfunction "AGND_AGND") (pintype "power_in"))
      (node (ref "U$1") (pin "GND") (pinfunction "GND_GND") (pintype "power_in"))
      (node (ref "U$1") (pin "GND1") (pinfunction "GND_GND1") (pintype "power_in"))
      (node (ref "U$1") (pin "GND2") (pinfunction "GND_GND2") (pintype "power_in"))
      (node (ref "U$10") (pin "3") (pinfunction "3_3") (pintype "bidirectional"))
      (node (ref "U$11") (pin "3") (pinfunction "3_3") (pintype "bidirectional"))
      (node (ref "U$12") (pin "3") (pinfunction "3_3") (pintype "bidirectional"))
      (node (ref "U$13") (pin "3") (pinfunction "3_3") (pintype "bidirectional"))
      (node (ref "U$14") (pin "3") (pinfunction "3_3") (pintype "bidirectional"))
      (node (ref "U$15") (pin "3") (pinfunction "3_3") (pintype "bidirectional"))
      (node (ref "U$16") (pin "3") (pinfunction "3_3") (pintype "bidirectional"))
      (node (ref "U$17") (pin "3") (pinfunction "3_3") (pintype "bidirectional"))
      (node (ref "U$2") (pin "3") (pinfunction "3_3") (pintype "bidirectional"))
      (node (ref "U$3") (pin "3") (pinfunction "3_3") (pintype "bidirectional"))
      (node (ref "U$4") (pin "3") (pinfunction "3_3") (pintype "bidirectional"))
      (node (ref "U$5") (pin "3") (pinfunction "3_3") (pintype "bidirectional"))
      (node (ref "U$6") (pin "3") (pinfunction "3_3") (pintype "bidirectional"))
      (node (ref "U$7") (pin "3") (pinfunction "3_3") (pintype "bidirectional"))
      (node (ref "U$8") (pin "3") (pinfunction "3_3") (pintype "bidirectional"))
      (node (ref "U$9") (pin "3") (pinfunction "3_3") (pintype "bidirectional"))
      (node (ref "U1") (pin "11") (pinfunction "V-_11") (pintype "power_in"))
      (node (ref "U2") (pin "11") (pinfunction "V-_11") (pintype "power_in"))
      (node (ref "U3") (pin "11") (pinfunction "V-_11") (pintype "power_in"))
      (node (ref "U4") (pin "11") (pinfunction "V-_11") (pintype "power_in"))
      (node (ref "U5") (pin "11") (pinfunction "V-_11") (pintype "power_in"))
      (node (ref "U6") (pin "11") (pinfunction "V-_11") (pintype "power_in"))
      (node (ref "U7") (pin "11") (pinfunction "V-_11") (pintype "power_in"))
      (node (ref "U8") (pin "11") (pinfunction "V-_11") (pintype "power_in"))
    )
    (net (code "36") (name "MIDI_OUT") (class "Default")
      (node (ref "R2") (pin "2") (pinfunction "2_2") (pintype "passive"))
      (node (ref "U$1") (pin "1") (pinfunction "1/TX1/T_1") (pintype "bidirectional"))
    )
    (net (code "37") (name "Net-(JP1-LEFT)") (class "Default")
      (node (ref "JP1") (pin "TIP") (pinfunction "LEFT_TIP") (pintype "bidirectional"))
      (node (ref "S1") (pin "P2") (pinfunction "5_P2") (pintype "bidirectional"))
    )
    (net (code "38") (name "Net-(JP1-RIGHT)") (class "Default")
      (node (ref "JP1") (pin "RING") (pinfunction "RIGHT_RING") (pintype "bidirectional"))
      (node (ref "S1") (pin "P1") (pinfunction "2_P1") (pintype "bidirectional"))
    )
    (net (code "39") (name "Net-(S1-1)") (class "Default")
      (node (ref "R1") (pin "1") (pinfunction "1_1") (pintype "passive"))
      (node (ref "S1") (pin "P1-TA") (pinfunction "1_P1-TA") (pintype "bidirectional"))
      (node (ref "S1") (pin "P2-TB") (pinfunction "6_P2-TB") (pintype "bidirectional"))
    )
    (net (code "40") (name "Net-(S1-3)") (class "Default")
      (node (ref "R2") (pin "1") (pinfunction "1_1") (pintype "passive"))
      (node (ref "S1") (pin "P1-TB") (pinfunction "3_P1-TB") (pintype "bidirectional"))
      (node (ref "S1") (pin "P2-TA") (pinfunction "4_P2-TA") (pintype "bidirectional"))
    )
    (net (code "41") (name "Net-(U1A--IN)") (class "Default")
      (node (ref "R7") (pin "1") (pinfunction "1_1") (pintype "passive"))
      (node (ref "U1") (pin "1") (pinfunction "OUT_1") (pintype "output"))
      (node (ref "U1") (pin "2") (pinfunction "-IN_2") (pintype "input"))
    )
    (net (code "42") (name "Net-(U1B-+IN)") (class "Default")
      (node (ref "R5") (pin "2") (pinfunction "2_2") (pintype "passive"))
      (node (ref "R6") (pin "2") (pinfunction "2_2") (pintype "passive"))
      (node (ref "U1") (pin "5") (pinfunction "+IN_5") (pintype "input"))
    )
    (net (code "43") (name "Net-(U1C-+IN)") (class "Default")
      (node (ref "R8") (pin "2") (pinfunction "2_2") (pintype "passive"))
      (node (ref "R9") (pin "2") (pinfunction "2_2") (pintype "passive"))
      (node (ref "U1") (pin "10") (pinfunction "+IN_10") (pintype "input"))
    )
    (net (code "44") (name "Net-(U1D--IN)") (class "Default")
      (node (ref "R12") (pin "1") (pinfunction "1_1") (pintype "passive"))
      (node (ref "U1") (pin "13") (pinfunction "-IN_13") (pintype "input"))
      (node (ref "U1") (pin "14") (pinfunction "OUT_14") (pintype "output"))
    )
    (net (code "45") (name "Net-(U2A--IN)") (class "Default")
      (node (ref "R52") (pin "1") (pinfunction "1_1") (pintype "passive"))
      (node (ref "U2") (pin "1") (pinfunction "OUT_1") (pintype "output"))
      (node (ref "U2") (pin "2") (pinfunction "-IN_2") (pintype "input"))
    )
    (net (code "46") (name "Net-(U2B-+IN)") (class "Default")
      (node (ref "R10") (pin "2") (pinfunction "2_2") (pintype "passive"))
      (node (ref "R11") (pin "2") (pinfunction "2_2") (pintype "passive"))
      (node (ref "U2") (pin "5") (pinfunction "+IN_5") (pintype "input"))
    )
    (net (code "47") (name "Net-(U2C-+IN)") (class "Default")
      (node (ref "R13") (pin "2") (pinfunction "2_2") (pintype "passive"))
      (node (ref "R14") (pin "2") (pinfunction "2_2") (pintype "passive"))
      (node (ref "U2") (pin "10") (pinfunction "+IN_10") (pintype "input"))
    )
    (net (code "48") (name "Net-(U2D--IN)") (class "Default")
      (node (ref "R45") (pin "1") (pinfunction "1_1") (pintype "passive"))
      (node (ref "U2") (pin "13") (pinfunction "-IN_13") (pintype "input"))
      (node (ref "U2") (pin "14") (pinfunction "OUT_14") (pintype "output"))
    )
    (net (code "49") (name "Net-(U3A--IN)") (class "Default")
      (node (ref "R17") (pin "1") (pinfunction "1_1") (pintype "passive"))
      (node (ref "U3") (pin "1") (pinfunction "OUT_1") (pintype "output"))
      (node (ref "U3") (pin "2") (pinfunction "-IN_2") (pintype "input"))
    )
    (net (code "50") (name "Net-(U3B-+IN)") (class "Default")
      (node (ref "R15") (pin "2") (pinfunction "2_2") (pintype "passive"))
      (node (ref "R16") (pin "2") (pinfunction "2_2") (pintype "passive"))
      (node (ref "U3") (pin "5") (pinfunction "+IN_5") (pintype "input"))
    )
    (net (code "51") (name "Net-(U3C-+IN)") (class "Default")
      (node (ref "R18") (pin "2") (pinfunction "2_2") (pintype "passive"))
      (node (ref "R19") (pin "2") (pinfunction "2_2") (pintype "passive"))
      (node (ref "U3") (pin "10") (pinfunction "+IN_10") (pintype "input"))
    )
    (net (code "52") (name "Net-(U3D--IN)") (class "Default")
      (node (ref "R47") (pin "1") (pinfunction "1_1") (pintype "passive"))
      (node (ref "U3") (pin "13") (pinfunction "-IN_13") (pintype "input"))
      (node (ref "U3") (pin "14") (pinfunction "OUT_14") (pintype "output"))
    )
    (net (code "53") (name "Net-(U4A--IN)") (class "Default")
      (node (ref "R22") (pin "1") (pinfunction "1_1") (pintype "passive"))
      (node (ref "U4") (pin "1") (pinfunction "OUT_1") (pintype "output"))
      (node (ref "U4") (pin "2") (pinfunction "-IN_2") (pintype "input"))
    )
    (net (code "54") (name "Net-(U4B-+IN)") (class "Default")
      (node (ref "R20") (pin "2") (pinfunction "2_2") (pintype "passive"))
      (node (ref "R21") (pin "2") (pinfunction "2_2") (pintype "passive"))
      (node (ref "U4") (pin "5") (pinfunction "+IN_5") (pintype "input"))
    )
    (net (code "55") (name "Net-(U4C-+IN)") (class "Default")
      (node (ref "R23") (pin "2") (pinfunction "2_2") (pintype "passive"))
      (node (ref "R24") (pin "2") (pinfunction "2_2") (pintype "passive"))
      (node (ref "U4") (pin "10") (pinfunction "+IN_10") (pintype "input"))
    )
    (net (code "56") (name "Net-(U4D--IN)") (class "Default")
      (node (ref "R46") (pin "1") (pinfunction "1_1") (pintype "passive"))
      (node (ref "U4") (pin "13") (pinfunction "-IN_13") (pintype "input"))
      (node (ref "U4") (pin "14") (pinfunction "OUT_14") (pintype "output"))
    )
    (net (code "57") (name "Net-(U5A--IN)") (class "Default")
      (node (ref "R27") (pin "1") (pinfunction "1_1") (pintype "passive"))
      (node (ref "U5") (pin "1") (pinfunction "OUT_1") (pintype "output"))
      (node (ref "U5") (pin "2") (pinfunction "-IN_2") (pintype "input"))
    )
    (net (code "58") (name "Net-(U5B-+IN)") (class "Default")
      (node (ref "R25") (pin "2") (pinfunction "2_2") (pintype "passive"))
      (node (ref "R26") (pin "2") (pinfunction "2_2") (pintype "passive"))
      (node (ref "U5") (pin "5") (pinfunction "+IN_5") (pintype "input"))
    )
    (net (code "59") (name "Net-(U5C-+IN)") (class "Default")
      (node (ref "R28") (pin "2") (pinfunction "2_2") (pintype "passive"))
      (node (ref "R29") (pin "2") (pinfunction "2_2") (pintype "passive"))
      (node (ref "U5") (pin "10") (pinfunction "+IN_10") (pintype "input"))
    )
    (net (code "60") (name "Net-(U5D--IN)") (class "Default")
      (node (ref "R48") (pin "1") (pinfunction "1_1") (pintype "passive"))
      (node (ref "U5") (pin "13") (pinfunction "-IN_13") (pintype "input"))
      (node (ref "U5") (pin "14") (pinfunction "OUT_14") (pintype "output"))
    )
    (net (code "61") (name "Net-(U6A--IN)") (class "Default")
      (node (ref "R32") (pin "1") (pinfunction "1_1") (pintype "passive"))
      (node (ref "U6") (pin "1") (pinfunction "OUT_1") (pintype "output"))
      (node (ref "U6") (pin "2") (pinfunction "-IN_2") (pintype "input"))
    )
    (net (code "62") (name "Net-(U6B-+IN)") (class "Default")
      (node (ref "R30") (pin "2") (pinfunction "2_2") (pintype "passive"))
      (node (ref "R31") (pin "2") (pinfunction "2_2") (pintype "passive"))
      (node (ref "U6") (pin "5") (pinfunction "+IN_5") (pintype "input"))
    )
    (net (code "63") (name "Net-(U6C-+IN)") (class "Default")
      (node (ref "R33") (pin "2") (pinfunction "2_2") (pintype "passive"))
      (node (ref "R34") (pin "2") (pinfunction "2_2") (pintype "passive"))
      (node (ref "U6") (pin "10") (pinfunction "+IN_10") (pintype "input"))
    )
    (net (code "64") (name "Net-(U6D--IN)") (class "Default")
      (node (ref "R49") (pin "1") (pinfunction "1_1") (pintype "passive"))
      (node (ref "U6") (pin "13") (pinfunction "-IN_13") (pintype "input"))
      (node (ref "U6") (pin "14") (pinfunction "OUT_14") (pintype "output"))
    )
    (net (code "65") (name "Net-(U7A--IN)") (class "Default")
      (node (ref "R37") (pin "1") (pinfunction "1_1") (pintype "passive"))
      (node (ref "U7") (pin "1") (pinfunction "OUT_1") (pintype "output"))
      (node (ref "U7") (pin "2") (pinfunction "-IN_2") (pintype "input"))
    )
    (net (code "66") (name "Net-(U7B-+IN)") (class "Default")
      (node (ref "R35") (pin "2") (pinfunction "2_2") (pintype "passive"))
      (node (ref "R36") (pin "2") (pinfunction "2_2") (pintype "passive"))
      (node (ref "U7") (pin "5") (pinfunction "+IN_5") (pintype "input"))
    )
    (net (code "67") (name "Net-(U7C-+IN)") (class "Default")
      (node (ref "R38") (pin "2") (pinfunction "2_2") (pintype "passive"))
      (node (ref "R39") (pin "2") (pinfunction "2_2") (pintype "passive"))
      (node (ref "U7") (pin "10") (pinfunction "+IN_10") (pintype "input"))
    )
    (net (code "68") (name "Net-(U7D--IN)") (class "Default")
      (node (ref "R50") (pin "1") (pinfunction "1_1") (pintype "passive"))
      (node (ref "U7") (pin "13") (pinfunction "-IN_13") (pintype "input"))
      (node (ref "U7") (pin "14") (pinfunction "OUT_14") (pintype "output"))
    )
    (net (code "69") (name "Net-(U8A--IN)") (class "Default")
      (node (ref "R42") (pin "1") (pinfunction "1_1") (pintype "passive"))
      (node (ref "U8") (pin "1") (pinfunction "OUT_1") (pintype "output"))
      (node (ref "U8") (pin "2") (pinfunction "-IN_2") (pintype "input"))
    )
    (net (code "70") (name "Net-(U8B-+IN)") (class "Default")
      (node (ref "R40") (pin "2") (pinfunction "2_2") (pintype "passive"))
      (node (ref "R41") (pin "2") (pinfunction "2_2") (pintype "passive"))
      (node (ref "U8") (pin "5") (pinfunction "+IN_5") (pintype "input"))
    )
    (net (code "71") (name "Net-(U8C-+IN)") (class "Default")
      (node (ref "R43") (pin "2") (pinfunction "2_2") (pintype "passive"))
      (node (ref "R44") (pin "2") (pinfunction "2_2") (pintype "passive"))
      (node (ref "U8") (pin "10") (pinfunction "+IN_10") (pintype "input"))
    )
    (net (code "72") (name "Net-(U8D--IN)") (class "Default")
      (node (ref "R51") (pin "1") (pinfunction "1_1") (pintype "passive"))
      (node (ref "U8") (pin "13") (pinfunction "-IN_13") (pintype "input"))
      (node (ref "U8") (pin "14") (pinfunction "OUT_14") (pintype "output"))
    )
    (net (code "73") (name "SCL") (class "Default")
      (node (ref "D3") (pin "C") (pinfunction "C_C") (pintype "passive"))
      (node (ref "D4") (pin "A") (pinfunction "A_A") (pintype "passive"))
      (node (ref "JP2") (pin "RING") (pinfunction "RIGHT_RING") (pintype "bidirectional"))
      (node (ref "R4") (pin "1") (pinfunction "1_1") (pintype "passive"))
      (node (ref "U$1") (pin "29") (pinfunction "29/A18/SCL1_29") (pintype "bidirectional"))
    )
    (net (code "74") (name "SDA") (class "Default")
      (node (ref "D1") (pin "C") (pinfunction "C_C") (pintype "passive"))
      (node (ref "D2") (pin "A") (pinfunction "A_A") (pintype "passive"))
      (node (ref "JP2") (pin "TIP") (pinfunction "LEFT_TIP") (pintype "bidirectional"))
      (node (ref "R3") (pin "1") (pinfunction "1_1") (pintype "passive"))
      (node (ref "U$1") (pin "30") (pinfunction "30/A19/SDA1_30") (pintype "bidirectional"))
    )
    (net (code "75") (name "VBAT") (class "Default")
      (node (ref "U$1") (pin "VBAT") (pinfunction "VBAT_VBAT") (pintype "power_in"))
    )
    (net (code "76") (name "VIN") (class "Default")
      (node (ref "U$1") (pin "VIN") (pinfunction "VIN_VIN") (pintype "power_in"))
    )
    (net (code "77") (name "W0") (class "Default")
      (node (ref "R5") (pin "1") (pinfunction "1_1") (pintype "passive"))
      (node (ref "U$17") (pin "2") (pinfunction "2_2") (pintype "bidirectional"))
      (node (ref "U1") (pin "3") (pinfunction "+IN_3") (pintype "input"))
    )
    (net (code "78") (name "W1") (class "Default")
      (node (ref "R9") (pin "1") (pinfunction "1_1") (pintype "passive"))
      (node (ref "U$16") (pin "2") (pinfunction "2_2") (pintype "bidirectional"))
      (node (ref "U1") (pin "12") (pinfunction "+IN_12") (pintype "input"))
    )
    (net (code "79") (name "W2") (class "Default")
      (node (ref "R10") (pin "1") (pinfunction "1_1") (pintype "passive"))
      (node (ref "U$15") (pin "2") (pinfunction "2_2") (pintype "bidirectional"))
      (node (ref "U2") (pin "3") (pinfunction "+IN_3") (pintype "input"))
    )
    (net (code "80") (name "W3") (class "Default")
      (node (ref "R14") (pin "1") (pinfunction "1_1") (pintype "passive"))
      (node (ref "U$14") (pin "2") (pinfunction "2_2") (pintype "bidirectional"))
      (node (ref "U2") (pin "12") (pinfunction "+IN_12") (pintype "input"))
    )
    (net (code "81") (name "W4") (class "Default")
      (node (ref "R15") (pin "1") (pinfunction "1_1") (pintype "passive"))
      (node (ref "U$13") (pin "2") (pinfunction "2_2") (pintype "bidirectional"))
      (node (ref "U3") (pin "3") (pinfunction "+IN_3") (pintype "input"))
    )
    (net (code "82") (name "W5") (class "Default")
      (node (ref "R19") (pin "1") (pinfunction "1_1") (pintype "passive"))
      (node (ref "U$12") (pin "2") (pinfunction "2_2") (pintype "bidirectional"))
      (node (ref "U3") (pin "12") (pinfunction "+IN_12") (pintype "input"))
    )
    (net (code "83") (name "W6") (class "Default")
      (node (ref "R20") (pin "1") (pinfunction "1_1") (pintype "passive"))
      (node (ref "U$11") (pin "2") (pinfunction "2_2") (pintype "bidirectional"))
      (node (ref "U4") (pin "3") (pinfunction "+IN_3") (pintype "input"))
    )
    (net (code "84") (name "W7") (class "Default")
      (node (ref "R24") (pin "1") (pinfunction "1_1") (pintype "passive"))
      (node (ref "U$10") (pin "2") (pinfunction "2_2") (pintype "bidirectional"))
      (node (ref "U4") (pin "12") (pinfunction "+IN_12") (pintype "input"))
    )
    (net (code "85") (name "W8") (class "Default")
      (node (ref "R25") (pin "1") (pinfunction "1_1") (pintype "passive"))
      (node (ref "U$9") (pin "2") (pinfunction "2_2") (pintype "bidirectional"))
      (node (ref "U5") (pin "3") (pinfunction "+IN_3") (pintype "input"))
    )
    (net (code "86") (name "W9") (class "Default")
      (node (ref "R29") (pin "1") (pinfunction "1_1") (pintype "passive"))
      (node (ref "U$8") (pin "2") (pinfunction "2_2") (pintype "bidirectional"))
      (node (ref "U5") (pin "12") (pinfunction "+IN_12") (pintype "input"))
    )
    (net (code "87") (name "W10") (class "Default")
      (node (ref "R30") (pin "1") (pinfunction "1_1") (pintype "passive"))
      (node (ref "U$7") (pin "2") (pinfunction "2_2") (pintype "bidirectional"))
      (node (ref "U6") (pin "3") (pinfunction "+IN_3") (pintype "input"))
    )
    (net (code "88") (name "W11") (class "Default")
      (node (ref "R34") (pin "1") (pinfunction "1_1") (pintype "passive"))
      (node (ref "U$6") (pin "2") (pinfunction "2_2") (pintype "bidirectional"))
      (node (ref "U6") (pin "12") (pinfunction "+IN_12") (pintype "input"))
    )
    (net (code "89") (name "W12") (class "Default")
      (node (ref "R35") (pin "1") (pinfunction "1_1") (pintype "passive"))
      (node (ref "U$5") (pin "2") (pinfunction "2_2") (pintype "bidirectional"))
      (node (ref "U7") (pin "3") (pinfunction "+IN_3") (pintype "input"))
    )
    (net (code "90") (name "W13") (class "Default")
      (node (ref "R39") (pin "1") (pinfunction "1_1") (pintype "passive"))
      (node (ref "U$4") (pin "2") (pinfunction "2_2") (pintype "bidirectional"))
      (node (ref "U7") (pin "12") (pinfunction "+IN_12") (pintype "input"))
    )
    (net (code "91") (name "W14") (class "Default")
      (node (ref "R40") (pin "1") (pinfunction "1_1") (pintype "passive"))
      (node (ref "U$3") (pin "2") (pinfunction "2_2") (pintype "bidirectional"))
      (node (ref "U8") (pin "3") (pinfunction "+IN_3") (pintype "input"))
    )
    (net (code "92") (name "W15") (class "Default")
      (node (ref "R44") (pin "1") (pinfunction "1_1") (pintype "passive"))
      (node (ref "U$2") (pin "2") (pinfunction "2_2") (pintype "bidirectional"))
      (node (ref "U8") (pin "12") (pinfunction "+IN_12") (pintype "input"))
    )
    (net (code "93") (name "unconnected-(J1-SWITCH-PadSW)") (class "Default")
      (node (ref "J1") (pin "SW") (pinfunction "SWITCH_SW") (pintype "passive"))
    )
    (net (code "94") (name "unconnected-(J2-SWITCH-PadSW)") (class "Default")
      (node (ref "J2") (pin "SW") (pinfunction "SWITCH_SW") (pintype "passive"))
    )
    (net (code "95") (name "unconnected-(J3-SWITCH-PadSW)") (class "Default")
      (node (ref "J3") (pin "SW") (pinfunction "SWITCH_SW") (pintype "passive"))
    )
    (net (code "96") (name "unconnected-(J4-SWITCH-PadSW)") (class "Default")
      (node (ref "J4") (pin "SW") (pinfunction "SWITCH_SW") (pintype "passive"))
    )
    (net (code "97") (name "unconnected-(J5-SWITCH-PadSW)") (class "Default")
      (node (ref "J5") (pin "SW") (pinfunction "SWITCH_SW") (pintype "passive"))
    )
    (net (code "98") (name "unconnected-(J6-SWITCH-PadSW)") (class "Default")
      (node (ref "J6") (pin "SW") (pinfunction "SWITCH_SW") (pintype "passive"))
    )
    (net (code "99") (name "unconnected-(J7-SWITCH-PadSW)") (class "Default")
      (node (ref "J7") (pin "SW") (pinfunction "SWITCH_SW") (pintype "passive"))
    )
    (net (code "100") (name "unconnected-(J8-SWITCH-PadSW)") (class "Default")
      (node (ref "J8") (pin "SW") (pinfunction "SWITCH_SW") (pintype "passive"))
    )
    (net (code "101") (name "unconnected-(J9-SWITCH-PadSW)") (class "Default")
      (node (ref "J9") (pin "SW") (pinfunction "SWITCH_SW") (pintype "passive"))
    )
    (net (code "102") (name "unconnected-(J10-SWITCH-PadSW)") (class "Default")
      (node (ref "J10") (pin "SW") (pinfunction "SWITCH_SW") (pintype "passive"))
    )
    (net (code "103") (name "unconnected-(J11-SWITCH-PadSW)") (class "Default")
      (node (ref "J11") (pin "SW") (pinfunction "SWITCH_SW") (pintype "passive"))
    )
    (net (code "104") (name "unconnected-(J12-SWITCH-PadSW)") (class "Default")
      (node (ref "J12") (pin "SW") (pinfunction "SWITCH_SW") (pintype "passive"))
    )
    (net (code "105") (name "unconnected-(J13-SWITCH-PadSW)") (class "Default")
      (node (ref "J13") (pin "SW") (pinfunction "SWITCH_SW") (pintype "passive"))
    )
    (net (code "106") (name "unconnected-(J14-SWITCH-PadSW)") (class "Default")
      (node (ref "J14") (pin "SW") (pinfunction "SWITCH_SW") (pintype "passive"))
    )
    (net (code "107") (name "unconnected-(J15-SWITCH-PadSW)") (class "Default")
      (node (ref "J15") (pin "SW") (pinfunction "SWITCH_SW") (pintype "passive"))
    )
    (net (code "108") (name "unconnected-(J16-SWITCH-PadSW)") (class "Default")
      (node (ref "J16") (pin "SW") (pinfunction "SWITCH_SW") (pintype "passive"))
    )
    (net (code "109") (name "unconnected-(U$1-0{slash}RX1{slash}T-Pad0)") (class "Default")
      (node (ref "U$1") (pin "0") (pinfunction "0/RX1/T_0") (pintype "bidirectional"))
    )
    (net (code "110") (name "unconnected-(U$1-3{slash}CAN-TX{slash}PWM-Pad3)") (class "Default")
      (node (ref "U$1") (pin "3") (pinfunction "3/CAN-TX/PWM_3") (pintype "bidirectional"))
    )
    (net (code "111") (name "unconnected-(U$1-4{slash}CAN-RX-PWM-Pad4)") (class "Default")
      (node (ref "U$1") (pin "4") (pinfunction "4/CAN-RX-PWM_4") (pintype "bidirectional"))
    )
    (net (code "112") (name "unconnected-(U$1-5{slash}PWM-Pad5)") (class "Default")
      (node (ref "U$1") (pin "5") (pinfunction "5/PWM_5") (pintype "bidirectional"))
    )
    (net (code "113") (name "unconnected-(U$1-6{slash}PWM-Pad6)") (class "Default")
      (node (ref "U$1") (pin "6") (pinfunction "6/PWM_6") (pintype "bidirectional"))
    )
    (net (code "114") (name "unconnected-(U$1-7{slash}RX3-Pad7)") (class "Default")
      (node (ref "U$1") (pin "7") (pinfunction "7/RX3_7") (pintype "bidirectional"))
    )
    (net (code "115") (name "unconnected-(U$1-8{slash}TX3-Pad8)") (class "Default")
      (node (ref "U$1") (pin "8") (pinfunction "8/TX3_8") (pintype "bidirectional"))
    )
    (net (code "116") (name "unconnected-(U$1-9{slash}RX2{slash}PWM-Pad9)") (class "Default")
      (node (ref "U$1") (pin "9") (pinfunction "9/RX2/PWM_9") (pintype "bidirectional"))
    )
    (net (code "117") (name "unconnected-(U$1-10{slash}TX2{slash}PWM-Pad10)") (class "Default")
      (node (ref "U$1") (pin "10") (pinfunction "10/TX2/PWM_10") (pintype "bidirectional"))
    )
    (net (code "118") (name "unconnected-(U$1-11{slash}MOSI-Pad11)") (class "Default")
      (node (ref "U$1") (pin "11") (pinfunction "11/MOSI_11") (pintype "bidirectional"))
    )
    (net (code "119") (name "unconnected-(U$1-12{slash}MISO-Pad12)") (class "Default")
      (node (ref "U$1") (pin "12") (pinfunction "12/MISO_12") (pintype "bidirectional"))
    )
    (net (code "120") (name "unconnected-(U$1-13{slash}SCK{slash}LED-Pad13)") (class "Default")
      (node (ref "U$1") (pin "13") (pinfunction "13/SCK/LED_13") (pintype "bidirectional"))
    )
    (net (code "121") (name "unconnected-(U$1-25{slash}T{slash}PWM-Pad25)") (class "Default")
      (node (ref "U$1") (pin "25") (pinfunction "25/T/PWM_25") (pintype "bidirectional"))
    )
    (net (code "122") (name "unconnected-(U$1-27{slash}A16-Pad27)") (class "Default")
      (node (ref "U$1") (pin "27") (pinfunction "27/A16_27") (pintype "bidirectional"))
    )
    (net (code "123") (name "unconnected-(U$1-28{slash}A17-Pad28)") (class "Default")
      (node (ref "U$1") (pin "28") (pinfunction "28/A17_28") (pintype "bidirectional"))
    )
    (net (code "124") (name "unconnected-(U$1-31{slash}A20-Pad31)") (class "Default")
      (node (ref "U$1") (pin "31") (pinfunction "31/A20_31") (pintype "bidirectional"))
    )
    (net (code "125") (name "unconnected-(U$1-32{slash}T{slash}PWM-Pad32)") (class "Default")
      (node (ref "U$1") (pin "32") (pinfunction "32/T/PWM_32") (pintype "bidirectional"))
    )
    (net (code "126") (name "unconnected-(U$1-33{slash}T-Pad33)") (class "Default")
      (node (ref "U$1") (pin "33") (pinfunction "33/T_33") (pintype "bidirectional"))
    )
    (net (code "127") (name "unconnected-(U$1-Pad2)") (class "Default")
      (node (ref "U$1") (pin "2") (pinfunction "2_2") (pintype "bidirectional"))
    )
    (net (code "128") (name "unconnected-(U$1-Pad24)") (class "Default")
      (node (ref "U$1") (pin "24") (pinfunction "24_24") (pintype "bidirectional"))
    )
    (net (code "129") (name "unconnected-(U$1-PadPGM)") (class "Default")
      (node (ref "U$1") (pin "PGM") (pinfunction "PGM_PGM") (pintype "bidirectional"))
    )
  )
)
